# 6_SWITCHING.net
KiCad netlist of a schematic drawn in Altium Designer
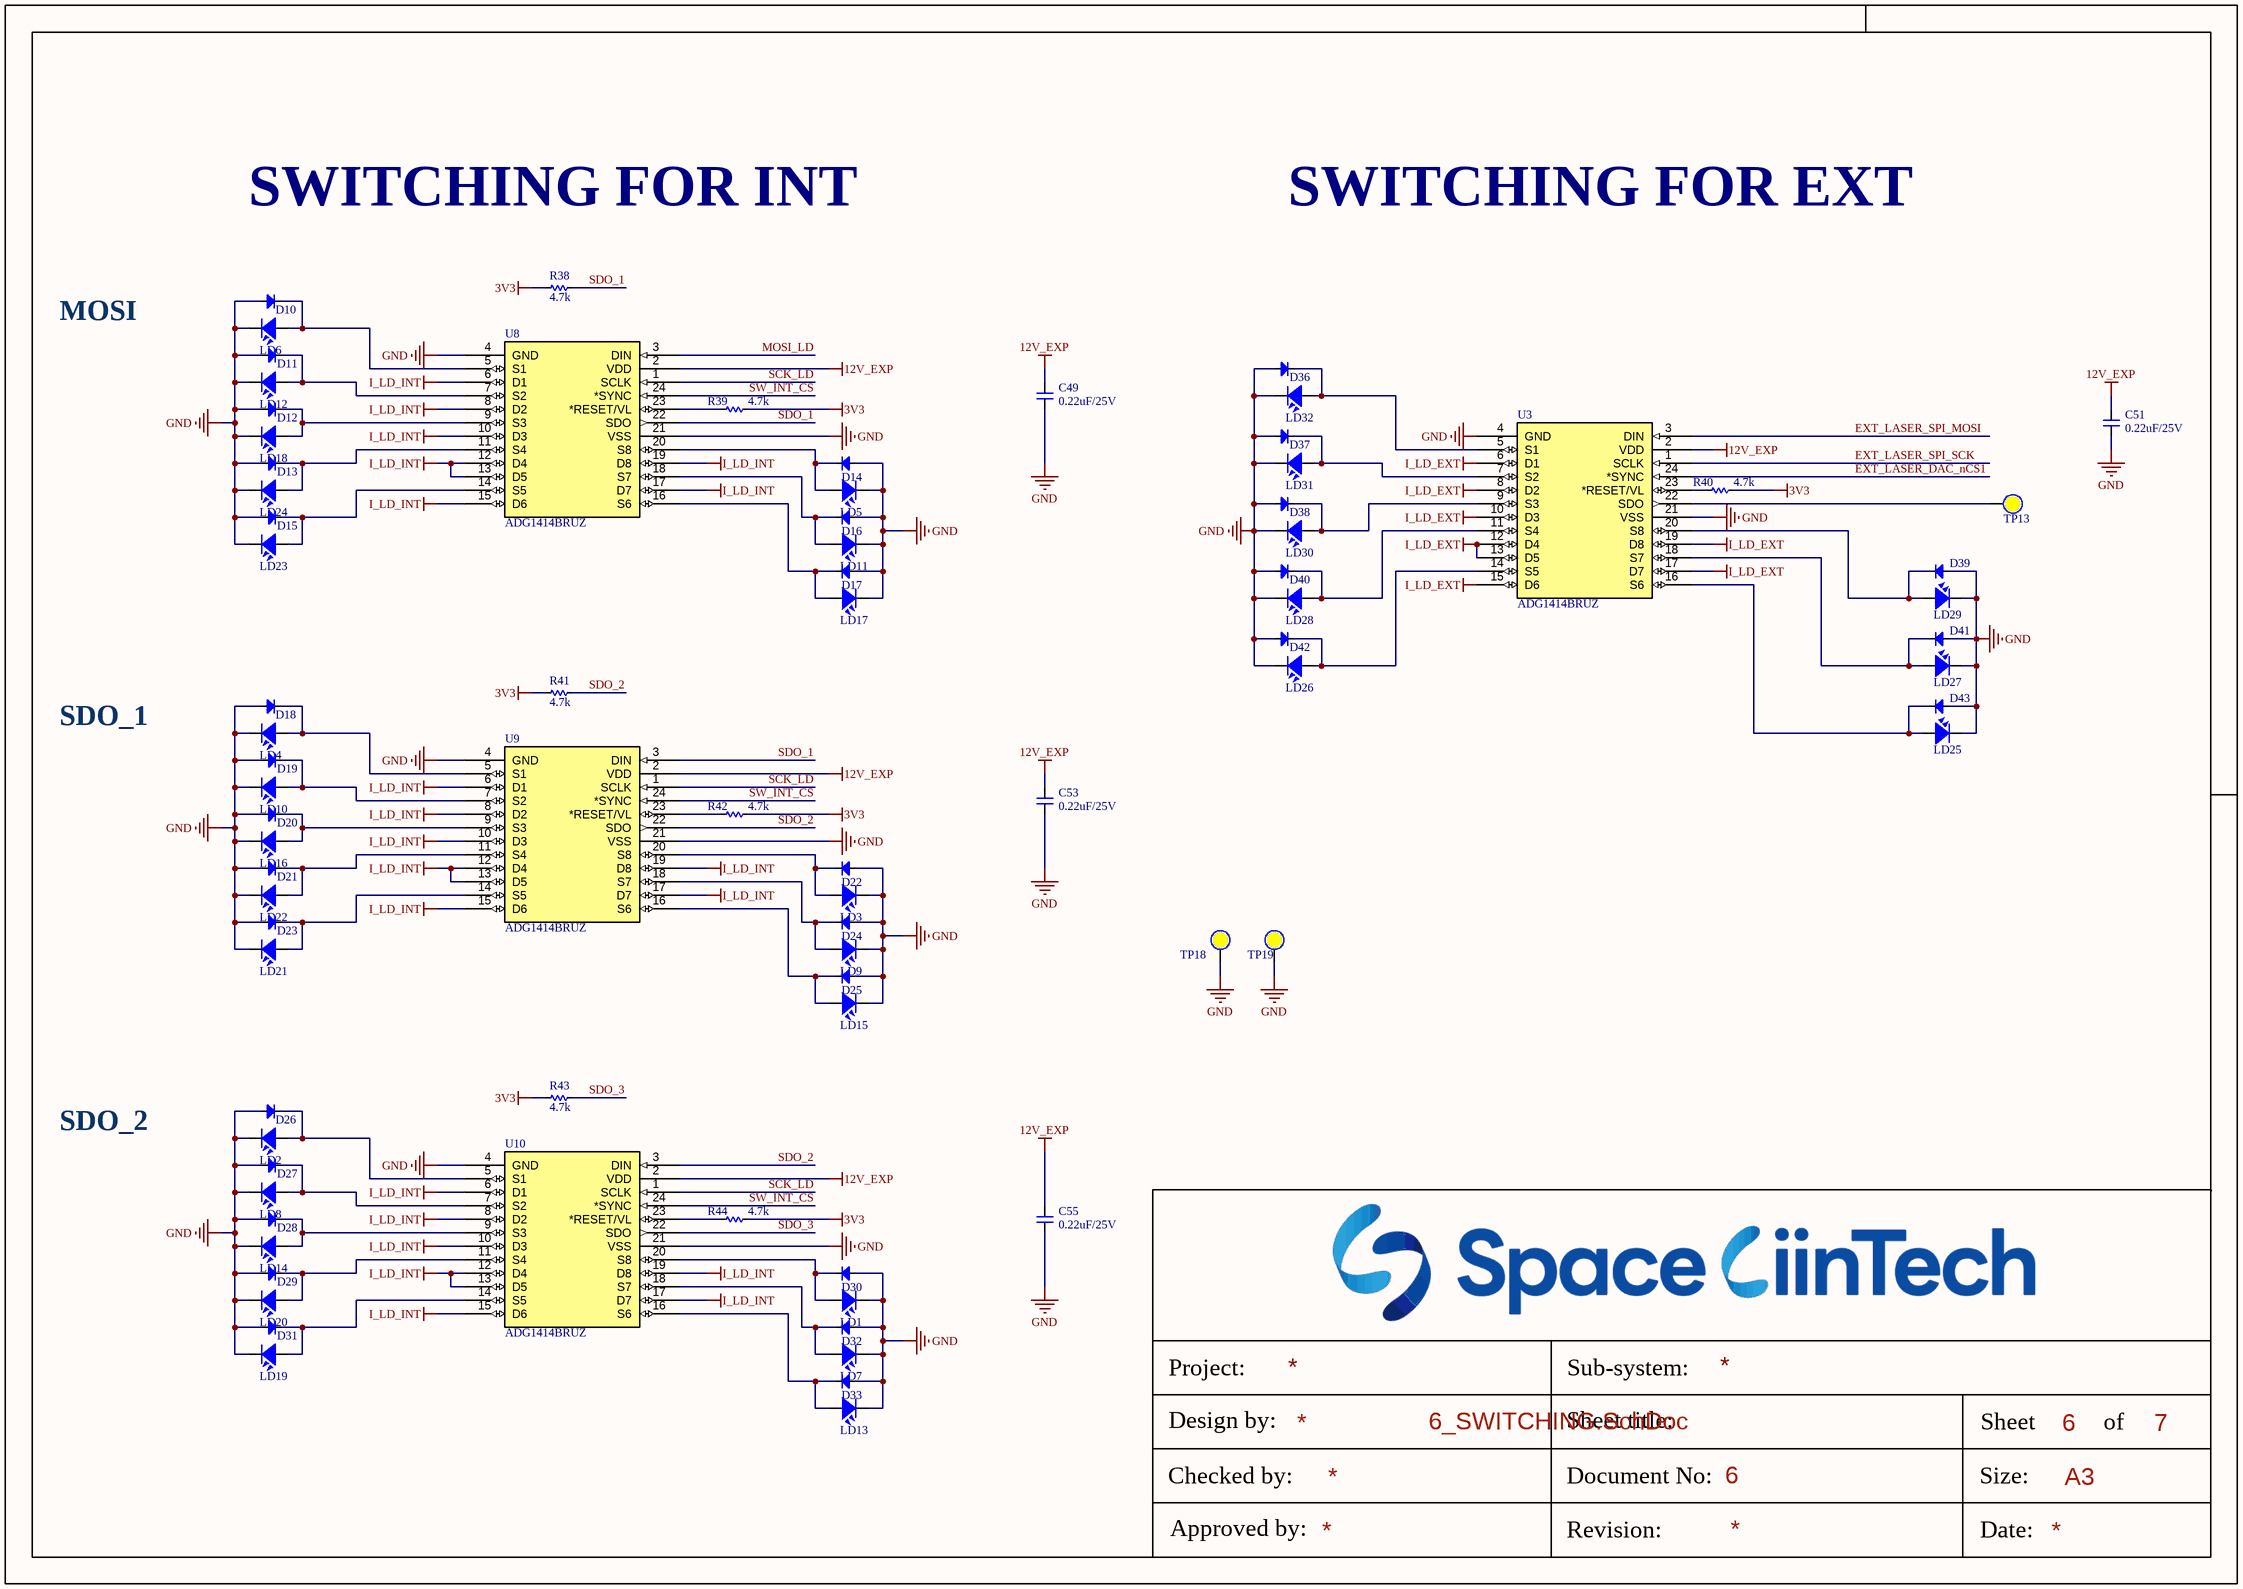
[diagram p0: 6_SWITCHING.SchDoc]

(export (version "E")
  (design (tool "Eeschema 10.0.6"))
  (components
    (comp (ref "C49")
      (value "0.22uF/25V")
      (footprint "CAP_C_1608X80")
      (description "CAP")
      (libsource (lib "LABLIB") (part "_CAP_C_2"))
    )
    (comp (ref "C51")
      (value "0.22uF/25V")
      (footprint "CAP_C_1608X80")
      (description "CAP")
      (libsource (lib "LABLIB") (part "_CAP_C_2"))
    )
    (comp (ref "C53")
      (value "0.22uF/25V")
      (footprint "CAP_C_1608X80")
      (description "CAP")
      (libsource (lib "LABLIB") (part "_CAP_C_2"))
    )
    (comp (ref "C55")
      (value "0.22uF/25V")
      (footprint "CAP_C_1608X80")
      (description "CAP")
      (libsource (lib "LABLIB") (part "_CAP_C_2"))
    )
    (comp (ref "D10")
      (value "1N4148W-TP")
      (footprint "SOD23")
      (fields (field (name "PUBLISHER") "Altium Limited"))
      (libsource (lib "LASER_LIB_SCHE") (part "Diode SMD"))
    )
    (comp (ref "D11")
      (value "1N4148W-TP")
      (footprint "SOD23")
      (fields (field (name "PUBLISHER") "Altium Limited"))
      (libsource (lib "LASER_LIB_SCHE") (part "Diode SMD"))
    )
    (comp (ref "D12")
      (value "1N4148W-TP")
      (footprint "SOD23")
      (fields (field (name "PUBLISHER") "Altium Limited"))
      (libsource (lib "LASER_LIB_SCHE") (part "Diode SMD"))
    )
    (comp (ref "D13")
      (value "1N4148W-TP")
      (footprint "SOD23")
      (fields (field (name "PUBLISHER") "Altium Limited"))
      (libsource (lib "LASER_LIB_SCHE") (part "Diode SMD"))
    )
    (comp (ref "D14")
      (value "1N4148W-TP")
      (footprint "SOD23")
      (fields (field (name "PUBLISHER") "Altium Limited"))
      (libsource (lib "LASER_LIB_SCHE") (part "Diode SMD"))
    )
    (comp (ref "D15")
      (value "1N4148W-TP")
      (footprint "SOD23")
      (fields (field (name "PUBLISHER") "Altium Limited"))
      (libsource (lib "LASER_LIB_SCHE") (part "Diode SMD"))
    )
    (comp (ref "D16")
      (value "1N4148W-TP")
      (footprint "SOD23")
      (fields (field (name "PUBLISHER") "Altium Limited"))
      (libsource (lib "LASER_LIB_SCHE") (part "Diode SMD"))
    )
    (comp (ref "D17")
      (value "1N4148W-TP")
      (footprint "SOD23")
      (fields (field (name "PUBLISHER") "Altium Limited"))
      (libsource (lib "LASER_LIB_SCHE") (part "Diode SMD"))
    )
    (comp (ref "D18")
      (value "1N4148W-TP")
      (footprint "SOD23")
      (fields (field (name "PUBLISHER") "Altium Limited"))
      (libsource (lib "LASER_LIB_SCHE") (part "Diode SMD"))
    )
    (comp (ref "D19")
      (value "1N4148W-TP")
      (footprint "SOD23")
      (fields (field (name "PUBLISHER") "Altium Limited"))
      (libsource (lib "LASER_LIB_SCHE") (part "Diode SMD"))
    )
    (comp (ref "D20")
      (value "1N4148W-TP")
      (footprint "SOD23")
      (fields (field (name "PUBLISHER") "Altium Limited"))
      (libsource (lib "LASER_LIB_SCHE") (part "Diode SMD"))
    )
    (comp (ref "D21")
      (value "1N4148W-TP")
      (footprint "SOD23")
      (fields (field (name "PUBLISHER") "Altium Limited"))
      (libsource (lib "LASER_LIB_SCHE") (part "Diode SMD"))
    )
    (comp (ref "D22")
      (value "1N4148W-TP")
      (footprint "SOD23")
      (fields (field (name "PUBLISHER") "Altium Limited"))
      (libsource (lib "LASER_LIB_SCHE") (part "Diode SMD"))
    )
    (comp (ref "D23")
      (value "1N4148W-TP")
      (footprint "SOD23")
      (fields (field (name "PUBLISHER") "Altium Limited"))
      (libsource (lib "LASER_LIB_SCHE") (part "Diode SMD"))
    )
    (comp (ref "D24")
      (value "1N4148W-TP")
      (footprint "SOD23")
      (fields (field (name "PUBLISHER") "Altium Limited"))
      (libsource (lib "LASER_LIB_SCHE") (part "Diode SMD"))
    )
    (comp (ref "D25")
      (value "1N4148W-TP")
      (footprint "SOD23")
      (fields (field (name "PUBLISHER") "Altium Limited"))
      (libsource (lib "LASER_LIB_SCHE") (part "Diode SMD"))
    )
    (comp (ref "D26")
      (value "1N4148W-TP")
      (footprint "SOD23")
      (fields (field (name "PUBLISHER") "Altium Limited"))
      (libsource (lib "LASER_LIB_SCHE") (part "Diode SMD"))
    )
    (comp (ref "D27")
      (value "1N4148W-TP")
      (footprint "SOD23")
      (fields (field (name "PUBLISHER") "Altium Limited"))
      (libsource (lib "LASER_LIB_SCHE") (part "Diode SMD"))
    )
    (comp (ref "D28")
      (value "1N4148W-TP")
      (footprint "SOD23")
      (fields (field (name "PUBLISHER") "Altium Limited"))
      (libsource (lib "LASER_LIB_SCHE") (part "Diode SMD"))
    )
    (comp (ref "D29")
      (value "1N4148W-TP")
      (footprint "SOD23")
      (fields (field (name "PUBLISHER") "Altium Limited"))
      (libsource (lib "LASER_LIB_SCHE") (part "Diode SMD"))
    )
    (comp (ref "D30")
      (value "1N4148W-TP")
      (footprint "SOD23")
      (fields (field (name "PUBLISHER") "Altium Limited"))
      (libsource (lib "LASER_LIB_SCHE") (part "Diode SMD"))
    )
    (comp (ref "D31")
      (value "1N4148W-TP")
      (footprint "SOD23")
      (fields (field (name "PUBLISHER") "Altium Limited"))
      (libsource (lib "LASER_LIB_SCHE") (part "Diode SMD"))
    )
    (comp (ref "D32")
      (value "1N4148W-TP")
      (footprint "SOD23")
      (fields (field (name "PUBLISHER") "Altium Limited"))
      (libsource (lib "LASER_LIB_SCHE") (part "Diode SMD"))
    )
    (comp (ref "D33")
      (value "1N4148W-TP")
      (footprint "SOD23")
      (fields (field (name "PUBLISHER") "Altium Limited"))
      (libsource (lib "LASER_LIB_SCHE") (part "Diode SMD"))
    )
    (comp (ref "D36")
      (value "1N4148W-TP")
      (footprint "SOD23")
      (fields (field (name "PUBLISHER") "Altium Limited"))
      (libsource (lib "LASER_LIB_SCHE") (part "Diode SMD"))
    )
    (comp (ref "D37")
      (value "1N4148W-TP")
      (footprint "SOD23")
      (fields (field (name "PUBLISHER") "Altium Limited"))
      (libsource (lib "LASER_LIB_SCHE") (part "Diode SMD"))
    )
    (comp (ref "D38")
      (value "1N4148W-TP")
      (footprint "SOD23")
      (fields (field (name "PUBLISHER") "Altium Limited"))
      (libsource (lib "LASER_LIB_SCHE") (part "Diode SMD"))
    )
    (comp (ref "D39")
      (value "1N4148W-TP")
      (footprint "SOD23")
      (fields (field (name "PUBLISHER") "Altium Limited"))
      (libsource (lib "LASER_LIB_SCHE") (part "Diode SMD"))
    )
    (comp (ref "D40")
      (value "1N4148W-TP")
      (footprint "SOD23")
      (fields (field (name "PUBLISHER") "Altium Limited"))
      (libsource (lib "LASER_LIB_SCHE") (part "Diode SMD"))
    )
    (comp (ref "D41")
      (value "1N4148W-TP")
      (footprint "SOD23")
      (fields (field (name "PUBLISHER") "Altium Limited"))
      (libsource (lib "LASER_LIB_SCHE") (part "Diode SMD"))
    )
    (comp (ref "D42")
      (value "1N4148W-TP")
      (footprint "SOD23")
      (fields (field (name "PUBLISHER") "Altium Limited"))
      (libsource (lib "LASER_LIB_SCHE") (part "Diode SMD"))
    )
    (comp (ref "D43")
      (value "1N4148W-TP")
      (footprint "SOD23")
      (fields (field (name "PUBLISHER") "Altium Limited"))
      (libsource (lib "LASER_LIB_SCHE") (part "Diode SMD"))
    )
    (comp (ref "LD1")
      (value "LaserDiode")
      (footprint "OPV302")
      (description "OPV302")
      (libsource (lib "LASER_LIB_SCHE") (part "LD"))
    )
    (comp (ref "LD2")
      (value "LaserDiode")
      (footprint "OPV302")
      (description "OPV302")
      (libsource (lib "LASER_LIB_SCHE") (part "LD"))
    )
    (comp (ref "LD3")
      (value "LaserDiode")
      (footprint "OPV302")
      (description "OPV302")
      (libsource (lib "LASER_LIB_SCHE") (part "LD"))
    )
    (comp (ref "LD4")
      (value "LaserDiode")
      (footprint "OPV302")
      (description "OPV302")
      (libsource (lib "LASER_LIB_SCHE") (part "LD"))
    )
    (comp (ref "LD5")
      (value "LaserDiode")
      (footprint "OPV302")
      (description "OPV302")
      (libsource (lib "LASER_LIB_SCHE") (part "LD"))
    )
    (comp (ref "LD6")
      (value "LaserDiode")
      (footprint "OPV302")
      (description "OPV302")
      (libsource (lib "LASER_LIB_SCHE") (part "LD"))
    )
    (comp (ref "LD7")
      (value "LaserDiode")
      (footprint "OPV302")
      (description "OPV302")
      (libsource (lib "LASER_LIB_SCHE") (part "LD"))
    )
    (comp (ref "LD8")
      (value "LaserDiode")
      (footprint "OPV302")
      (description "OPV302")
      (libsource (lib "LASER_LIB_SCHE") (part "LD"))
    )
    (comp (ref "LD9")
      (value "LaserDiode")
      (footprint "OPV302")
      (description "OPV302")
      (libsource (lib "LASER_LIB_SCHE") (part "LD"))
    )
    (comp (ref "LD10")
      (value "LaserDiode")
      (footprint "OPV302")
      (description "OPV302")
      (libsource (lib "LASER_LIB_SCHE") (part "LD"))
    )
    (comp (ref "LD11")
      (value "LaserDiode")
      (footprint "OPV302")
      (description "OPV302")
      (libsource (lib "LASER_LIB_SCHE") (part "LD"))
    )
    (comp (ref "LD12")
      (value "LaserDiode")
      (footprint "OPV302")
      (description "OPV302")
      (libsource (lib "LASER_LIB_SCHE") (part "LD"))
    )
    (comp (ref "LD13")
      (value "LaserDiode")
      (footprint "OPV302")
      (description "OPV302")
      (libsource (lib "LASER_LIB_SCHE") (part "LD"))
    )
    (comp (ref "LD14")
      (value "LaserDiode")
      (footprint "OPV302")
      (description "OPV302")
      (libsource (lib "LASER_LIB_SCHE") (part "LD"))
    )
    (comp (ref "LD15")
      (value "LaserDiode")
      (footprint "OPV302")
      (description "OPV302")
      (libsource (lib "LASER_LIB_SCHE") (part "LD"))
    )
    (comp (ref "LD16")
      (value "LaserDiode")
      (footprint "OPV302")
      (description "OPV302")
      (libsource (lib "LASER_LIB_SCHE") (part "LD"))
    )
    (comp (ref "LD17")
      (value "LaserDiode")
      (footprint "OPV302")
      (description "OPV302")
      (libsource (lib "LASER_LIB_SCHE") (part "LD"))
    )
    (comp (ref "LD18")
      (value "LaserDiode")
      (footprint "OPV302")
      (description "OPV302")
      (libsource (lib "LASER_LIB_SCHE") (part "LD"))
    )
    (comp (ref "LD19")
      (value "LaserDiode")
      (footprint "OPV302")
      (description "OPV302")
      (libsource (lib "LASER_LIB_SCHE") (part "LD"))
    )
    (comp (ref "LD20")
      (value "LaserDiode")
      (footprint "OPV302")
      (description "OPV302")
      (libsource (lib "LASER_LIB_SCHE") (part "LD"))
    )
    (comp (ref "LD21")
      (value "LaserDiode")
      (footprint "OPV302")
      (description "OPV302")
      (libsource (lib "LASER_LIB_SCHE") (part "LD"))
    )
    (comp (ref "LD22")
      (value "LaserDiode")
      (footprint "OPV302")
      (description "OPV302")
      (libsource (lib "LASER_LIB_SCHE") (part "LD"))
    )
    (comp (ref "LD23")
      (value "LaserDiode")
      (footprint "OPV302")
      (description "OPV302")
      (libsource (lib "LASER_LIB_SCHE") (part "LD"))
    )
    (comp (ref "LD24")
      (value "LaserDiode")
      (footprint "OPV302")
      (description "OPV302")
      (libsource (lib "LASER_LIB_SCHE") (part "LD"))
    )
    (comp (ref "LD25")
      (value "LaserDiode")
      (footprint "RLD65NZX1")
      (description "RLD65NZX1")
      (libsource (lib "LASER_LIB_SCHE") (part "LD_RLD65NZX1"))
    )
    (comp (ref "LD26")
      (value "LaserDiode")
      (footprint "RLD65NZX1")
      (description "RLD65NZX1")
      (libsource (lib "LASER_LIB_SCHE") (part "LD_RLD65NZX1"))
    )
    (comp (ref "LD27")
      (value "LaserDiode")
      (footprint "RLD65NZX1")
      (description "RLD65NZX1")
      (libsource (lib "LASER_LIB_SCHE") (part "LD_RLD65NZX1"))
    )
    (comp (ref "LD28")
      (value "LaserDiode")
      (footprint "RLD65NZX1")
      (description "RLD65NZX1")
      (libsource (lib "LASER_LIB_SCHE") (part "LD_RLD65NZX1"))
    )
    (comp (ref "LD29")
      (value "LaserDiode")
      (footprint "RLD65NZX1")
      (description "RLD65NZX1")
      (libsource (lib "LASER_LIB_SCHE") (part "LD_RLD65NZX1"))
    )
    (comp (ref "LD30")
      (value "LaserDiode")
      (footprint "RLD65NZX1")
      (description "RLD65NZX1")
      (libsource (lib "LASER_LIB_SCHE") (part "LD_RLD65NZX1"))
    )
    (comp (ref "LD31")
      (value "LaserDiode")
      (footprint "RLD65NZX1")
      (description "RLD65NZX1")
      (libsource (lib "LASER_LIB_SCHE") (part "LD_RLD65NZX1"))
    )
    (comp (ref "LD32")
      (value "LaserDiode")
      (footprint "RLD65NZX1")
      (description "RLD65NZX1")
      (libsource (lib "LASER_LIB_SCHE") (part "LD_RLD65NZX1"))
    )
    (comp (ref "R38")
      (value "4.7k")
      (footprint "RES_C_1608X60")
      (description "RES")
      (libsource (lib "LABLIB") (part "_RES_B_2"))
    )
    (comp (ref "R39")
      (value "4.7k")
      (footprint "RES_C_1608X60")
      (description "RES")
      (libsource (lib "LABLIB") (part "_RES_B_2"))
    )
    (comp (ref "R40")
      (value "4.7k")
      (footprint "RES_C_1608X60")
      (description "RES")
      (libsource (lib "LABLIB") (part "_RES_B_2"))
    )
    (comp (ref "R41")
      (value "4.7k")
      (footprint "RES_C_1608X60")
      (description "RES")
      (libsource (lib "LABLIB") (part "_RES_B_2"))
    )
    (comp (ref "R42")
      (value "4.7k")
      (footprint "RES_C_1608X60")
      (description "RES")
      (libsource (lib "LABLIB") (part "_RES_B_2"))
    )
    (comp (ref "R43")
      (value "4.7k")
      (footprint "RES_C_1608X60")
      (description "RES")
      (libsource (lib "LABLIB") (part "_RES_B_2"))
    )
    (comp (ref "R44")
      (value "4.7k")
      (footprint "RES_C_1608X60")
      (description "RES")
      (libsource (lib "LABLIB") (part "_RES_B_2"))
    )
    (comp (ref "TP13")
      (value "~")
      (footprint "Testpoint_80")
      (description "Test Point")
      (libsource (lib "LASER_LIB_SCHE") (part "Test Point"))
    )
    (comp (ref "TP18")
      (value "~")
      (footprint "Testpoint_80")
      (description "Test Point")
      (libsource (lib "") (part "Test Point_1"))
    )
    (comp (ref "TP19")
      (value "~")
      (footprint "Testpoint_80")
      (description "Test Point")
      (libsource (lib "") (part "Test Point_1"))
    )
    (comp (ref "U3")
      (value "ADG1414BRUZ")
      (footprint "TSSOP24")
      (libsource (lib "LASER_LIB_SCHE") (part "ADG1414BRUZ"))
    )
    (comp (ref "U8")
      (value "ADG1414BRUZ")
      (footprint "TSSOP24")
      (libsource (lib "LASER_LIB_SCHE") (part "ADG1414BRUZ"))
    )
    (comp (ref "U9")
      (value "ADG1414BRUZ")
      (footprint "TSSOP24")
      (libsource (lib "LASER_LIB_SCHE") (part "ADG1414BRUZ"))
    )
    (comp (ref "U10")
      (value "ADG1414BRUZ")
      (footprint "TSSOP24")
      (libsource (lib "LASER_LIB_SCHE") (part "ADG1414BRUZ"))
    )
  )
  (nets
    (net (code "1") (name "/EXT_LASER_DAC_nCS1") (class "Default")
      (node (ref "U3") (pin "24") (pinfunction "*SYNC_24") (pintype "input"))
    )
    (net (code "2") (name "/EXT_LASER_SPI_MOSI") (class "Default")
      (node (ref "U3") (pin "3") (pinfunction "DIN_3") (pintype "input"))
    )
    (net (code "3") (name "/EXT_LASER_SPI_SCK") (class "Default")
      (node (ref "U3") (pin "1") (pinfunction "SCLK_1") (pintype "input"))
    )
    (net (code "4") (name "/MOSI_LD") (class "Default")
      (node (ref "U8") (pin "3") (pinfunction "DIN_3") (pintype "input"))
    )
    (net (code "5") (name "/SCK_LD") (class "Default")
      (node (ref "U10") (pin "1") (pinfunction "SCLK_1") (pintype "input"))
      (node (ref "U8") (pin "1") (pinfunction "SCLK_1") (pintype "input"))
      (node (ref "U9") (pin "1") (pinfunction "SCLK_1") (pintype "input"))
    )
    (net (code "6") (name "/SDO_1") (class "Default")
      (node (ref "R38") (pin "2") (pinfunction "2_2") (pintype "passive"))
      (node (ref "U8") (pin "22") (pinfunction "SDO_22") (pintype "output"))
      (node (ref "U9") (pin "3") (pinfunction "DIN_3") (pintype "input"))
    )
    (net (code "7") (name "/SDO_2") (class "Default")
      (node (ref "R41") (pin "2") (pinfunction "2_2") (pintype "passive"))
      (node (ref "U10") (pin "3") (pinfunction "DIN_3") (pintype "input"))
      (node (ref "U9") (pin "22") (pinfunction "SDO_22") (pintype "output"))
    )
    (net (code "8") (name "/SDO_3") (class "Default")
      (node (ref "R43") (pin "2") (pinfunction "2_2") (pintype "passive"))
      (node (ref "U10") (pin "22") (pinfunction "SDO_22") (pintype "output"))
    )
    (net (code "9") (name "/SW_INT_CS") (class "Default")
      (node (ref "U10") (pin "24") (pinfunction "*SYNC_24") (pintype "input"))
      (node (ref "U8") (pin "24") (pinfunction "*SYNC_24") (pintype "input"))
      (node (ref "U9") (pin "24") (pinfunction "*SYNC_24") (pintype "input"))
    )
    (net (code "10") (name "3V3") (class "Default")
      (node (ref "R38") (pin "1") (pinfunction "1_1") (pintype "passive"))
      (node (ref "R39") (pin "2") (pinfunction "2_2") (pintype "passive"))
      (node (ref "R40") (pin "2") (pinfunction "2_2") (pintype "passive"))
      (node (ref "R41") (pin "1") (pinfunction "1_1") (pintype "passive"))
      (node (ref "R42") (pin "2") (pinfunction "2_2") (pintype "passive"))
      (node (ref "R43") (pin "1") (pinfunction "1_1") (pintype "passive"))
      (node (ref "R44") (pin "2") (pinfunction "2_2") (pintype "passive"))
    )
    (net (code "11") (name "12V_EXP") (class "Default")
      (node (ref "C49") (pin "2") (pinfunction "2_2") (pintype "passive"))
      (node (ref "C51") (pin "2") (pinfunction "2_2") (pintype "passive"))
      (node (ref "C53") (pin "2") (pinfunction "2_2") (pintype "passive"))
      (node (ref "C55") (pin "2") (pinfunction "2_2") (pintype "passive"))
      (node (ref "U10") (pin "2") (pinfunction "VDD_2") (pintype "power_in"))
      (node (ref "U3") (pin "2") (pinfunction "VDD_2") (pintype "power_in"))
      (node (ref "U8") (pin "2") (pinfunction "VDD_2") (pintype "power_in"))
      (node (ref "U9") (pin "2") (pinfunction "VDD_2") (pintype "power_in"))
    )
    (net (code "12") (name "GND") (class "Default")
      (node (ref "C49") (pin "1") (pinfunction "1_1") (pintype "passive"))
      (node (ref "C51") (pin "1") (pinfunction "1_1") (pintype "passive"))
      (node (ref "C53") (pin "1") (pinfunction "1_1") (pintype "passive"))
      (node (ref "C55") (pin "1") (pinfunction "1_1") (pintype "passive"))
      (node (ref "D10") (pin "1") (pinfunction "A_1") (pintype "passive"))
      (node (ref "D11") (pin "1") (pinfunction "A_1") (pintype "passive"))
      (node (ref "D12") (pin "1") (pinfunction "A_1") (pintype "passive"))
      (node (ref "D13") (pin "1") (pinfunction "A_1") (pintype "passive"))
      (node (ref "D14") (pin "1") (pinfunction "A_1") (pintype "passive"))
      (node (ref "D15") (pin "1") (pinfunction "A_1") (pintype "passive"))
      (node (ref "D16") (pin "1") (pinfunction "A_1") (pintype "passive"))
      (node (ref "D17") (pin "1") (pinfunction "A_1") (pintype "passive"))
      (node (ref "D18") (pin "1") (pinfunction "A_1") (pintype "passive"))
      (node (ref "D19") (pin "1") (pinfunction "A_1") (pintype "passive"))
      (node (ref "D20") (pin "1") (pinfunction "A_1") (pintype "passive"))
      (node (ref "D21") (pin "1") (pinfunction "A_1") (pintype "passive"))
      (node (ref "D22") (pin "1") (pinfunction "A_1") (pintype "passive"))
      (node (ref "D23") (pin "1") (pinfunction "A_1") (pintype "passive"))
      (node (ref "D24") (pin "1") (pinfunction "A_1") (pintype "passive"))
      (node (ref "D25") (pin "1") (pinfunction "A_1") (pintype "passive"))
      (node (ref "D26") (pin "1") (pinfunction "A_1") (pintype "passive"))
      (node (ref "D27") (pin "1") (pinfunction "A_1") (pintype "passive"))
      (node (ref "D28") (pin "1") (pinfunction "A_1") (pintype "passive"))
      (node (ref "D29") (pin "1") (pinfunction "A_1") (pintype "passive"))
      (node (ref "D30") (pin "1") (pinfunction "A_1") (pintype "passive"))
      (node (ref "D31") (pin "1") (pinfunction "A_1") (pintype "passive"))
      (node (ref "D32") (pin "1") (pinfunction "A_1") (pintype "passive"))
      (node (ref "D33") (pin "1") (pinfunction "A_1") (pintype "passive"))
      (node (ref "D36") (pin "1") (pinfunction "A_1") (pintype "passive"))
      (node (ref "D37") (pin "1") (pinfunction "A_1") (pintype "passive"))
      (node (ref "D38") (pin "1") (pinfunction "A_1") (pintype "passive"))
      (node (ref "D39") (pin "1") (pinfunction "A_1") (pintype "passive"))
      (node (ref "D40") (pin "1") (pinfunction "A_1") (pintype "passive"))
      (node (ref "D41") (pin "1") (pinfunction "A_1") (pintype "passive"))
      (node (ref "D42") (pin "1") (pinfunction "A_1") (pintype "passive"))
      (node (ref "D43") (pin "1") (pinfunction "A_1") (pintype "passive"))
      (node (ref "LD1") (pin "2") (pinfunction "2_2") (pintype "passive"))
      (node (ref "LD10") (pin "2") (pinfunction "2_2") (pintype "passive"))
      (node (ref "LD11") (pin "2") (pinfunction "2_2") (pintype "passive"))
      (node (ref "LD12") (pin "2") (pinfunction "2_2") (pintype "passive"))
      (node (ref "LD13") (pin "2") (pinfunction "2_2") (pintype "passive"))
      (node (ref "LD14") (pin "2") (pinfunction "2_2") (pintype "passive"))
      (node (ref "LD15") (pin "2") (pinfunction "2_2") (pintype "passive"))
      (node (ref "LD16") (pin "2") (pinfunction "2_2") (pintype "passive"))
      (node (ref "LD17") (pin "2") (pinfunction "2_2") (pintype "passive"))
      (node (ref "LD18") (pin "2") (pinfunction "2_2") (pintype "passive"))
      (node (ref "LD19") (pin "2") (pinfunction "2_2") (pintype "passive"))
      (node (ref "LD2") (pin "2") (pinfunction "2_2") (pintype "passive"))
      (node (ref "LD20") (pin "2") (pinfunction "2_2") (pintype "passive"))
      (node (ref "LD21") (pin "2") (pinfunction "2_2") (pintype "passive"))
      (node (ref "LD22") (pin "2") (pinfunction "2_2") (pintype "passive"))
      (node (ref "LD23") (pin "2") (pinfunction "2_2") (pintype "passive"))
      (node (ref "LD24") (pin "2") (pinfunction "2_2") (pintype "passive"))
      (node (ref "LD25") (pin "1") (pinfunction "1_1") (pintype "passive"))
      (node (ref "LD26") (pin "1") (pinfunction "1_1") (pintype "passive"))
      (node (ref "LD27") (pin "1") (pinfunction "1_1") (pintype "passive"))
      (node (ref "LD28") (pin "1") (pinfunction "1_1") (pintype "passive"))
      (node (ref "LD29") (pin "1") (pinfunction "1_1") (pintype "passive"))
      (node (ref "LD3") (pin "2") (pinfunction "2_2") (pintype "passive"))
      (node (ref "LD30") (pin "1") (pinfunction "1_1") (pintype "passive"))
      (node (ref "LD31") (pin "1") (pinfunction "1_1") (pintype "passive"))
      (node (ref "LD32") (pin "1") (pinfunction "1_1") (pintype "passive"))
      (node (ref "LD4") (pin "2") (pinfunction "2_2") (pintype "passive"))
      (node (ref "LD5") (pin "2") (pinfunction "2_2") (pintype "passive"))
      (node (ref "LD6") (pin "2") (pinfunction "2_2") (pintype "passive"))
      (node (ref "LD7") (pin "2") (pinfunction "2_2") (pintype "passive"))
      (node (ref "LD8") (pin "2") (pinfunction "2_2") (pintype "passive"))
      (node (ref "LD9") (pin "2") (pinfunction "2_2") (pintype "passive"))
      (node (ref "TP18") (pin "1") (pinfunction "1_1") (pintype "passive"))
      (node (ref "TP19") (pin "1") (pinfunction "1_1") (pintype "passive"))
      (node (ref "U10") (pin "21") (pinfunction "VSS_21") (pintype "power_in"))
      (node (ref "U10") (pin "4") (pinfunction "GND_4") (pintype "power_in"))
      (node (ref "U3") (pin "21") (pinfunction "VSS_21") (pintype "power_in"))
      (node (ref "U3") (pin "4") (pinfunction "GND_4") (pintype "power_in"))
      (node (ref "U8") (pin "21") (pinfunction "VSS_21") (pintype "power_in"))
      (node (ref "U8") (pin "4") (pinfunction "GND_4") (pintype "power_in"))
      (node (ref "U9") (pin "21") (pinfunction "VSS_21") (pintype "power_in"))
      (node (ref "U9") (pin "4") (pinfunction "GND_4") (pintype "power_in"))
    )
    (net (code "13") (name "I_LD_EXT") (class "Default")
      (node (ref "U3") (pin "10") (pinfunction "D3_10") (pintype "bidirectional"))
      (node (ref "U3") (pin "12") (pinfunction "D4_12") (pintype "bidirectional"))
      (node (ref "U3") (pin "13") (pinfunction "D5_13") (pintype "bidirectional"))
      (node (ref "U3") (pin "15") (pinfunction "D6_15") (pintype "bidirectional"))
      (node (ref "U3") (pin "17") (pinfunction "D7_17") (pintype "bidirectional"))
      (node (ref "U3") (pin "19") (pinfunction "D8_19") (pintype "bidirectional"))
      (node (ref "U3") (pin "6") (pinfunction "D1_6") (pintype "bidirectional"))
      (node (ref "U3") (pin "8") (pinfunction "D2_8") (pintype "bidirectional"))
    )
    (net (code "14") (name "I_LD_INT") (class "Default")
      (node (ref "U10") (pin "10") (pinfunction "D3_10") (pintype "bidirectional"))
      (node (ref "U10") (pin "12") (pinfunction "D4_12") (pintype "bidirectional"))
      (node (ref "U10") (pin "13") (pinfunction "D5_13") (pintype "bidirectional"))
      (node (ref "U10") (pin "15") (pinfunction "D6_15") (pintype "bidirectional"))
      (node (ref "U10") (pin "17") (pinfunction "D7_17") (pintype "bidirectional"))
      (node (ref "U10") (pin "19") (pinfunction "D8_19") (pintype "bidirectional"))
      (node (ref "U10") (pin "6") (pinfunction "D1_6") (pintype "bidirectional"))
      (node (ref "U10") (pin "8") (pinfunction "D2_8") (pintype "bidirectional"))
      (node (ref "U8") (pin "10") (pinfunction "D3_10") (pintype "bidirectional"))
      (node (ref "U8") (pin "12") (pinfunction "D4_12") (pintype "bidirectional"))
      (node (ref "U8") (pin "13") (pinfunction "D5_13") (pintype "bidirectional"))
      (node (ref "U8") (pin "15") (pinfunction "D6_15") (pintype "bidirectional"))
      (node (ref "U8") (pin "17") (pinfunction "D7_17") (pintype "bidirectional"))
      (node (ref "U8") (pin "19") (pinfunction "D8_19") (pintype "bidirectional"))
      (node (ref "U8") (pin "6") (pinfunction "D1_6") (pintype "bidirectional"))
      (node (ref "U8") (pin "8") (pinfunction "D2_8") (pintype "bidirectional"))
      (node (ref "U9") (pin "10") (pinfunction "D3_10") (pintype "bidirectional"))
      (node (ref "U9") (pin "12") (pinfunction "D4_12") (pintype "bidirectional"))
      (node (ref "U9") (pin "13") (pinfunction "D5_13") (pintype "bidirectional"))
      (node (ref "U9") (pin "15") (pinfunction "D6_15") (pintype "bidirectional"))
      (node (ref "U9") (pin "17") (pinfunction "D7_17") (pintype "bidirectional"))
      (node (ref "U9") (pin "19") (pinfunction "D8_19") (pintype "bidirectional"))
      (node (ref "U9") (pin "6") (pinfunction "D1_6") (pintype "bidirectional"))
      (node (ref "U9") (pin "8") (pinfunction "D2_8") (pintype "bidirectional"))
    )
    (net (code "15") (name "Net-(D10-K)") (class "Default")
      (node (ref "D10") (pin "2") (pinfunction "K_2") (pintype "passive"))
      (node (ref "LD6") (pin "1") (pinfunction "1_1") (pintype "passive"))
      (node (ref "U8") (pin "5") (pinfunction "S1_5") (pintype "bidirectional"))
    )
    (net (code "16") (name "Net-(D11-K)") (class "Default")
      (node (ref "D11") (pin "2") (pinfunction "K_2") (pintype "passive"))
      (node (ref "LD12") (pin "1") (pinfunction "1_1") (pintype "passive"))
      (node (ref "U8") (pin "7") (pinfunction "S2_7") (pintype "bidirectional"))
    )
    (net (code "17") (name "Net-(D12-K)") (class "Default")
      (node (ref "D12") (pin "2") (pinfunction "K_2") (pintype "passive"))
      (node (ref "LD18") (pin "1") (pinfunction "1_1") (pintype "passive"))
      (node (ref "U8") (pin "9") (pinfunction "S3_9") (pintype "bidirectional"))
    )
    (net (code "18") (name "Net-(D13-K)") (class "Default")
      (node (ref "D13") (pin "2") (pinfunction "K_2") (pintype "passive"))
      (node (ref "LD24") (pin "1") (pinfunction "1_1") (pintype "passive"))
      (node (ref "U8") (pin "11") (pinfunction "S4_11") (pintype "bidirectional"))
    )
    (net (code "19") (name "Net-(D14-K)") (class "Default")
      (node (ref "D14") (pin "2") (pinfunction "K_2") (pintype "passive"))
      (node (ref "LD5") (pin "1") (pinfunction "1_1") (pintype "passive"))
      (node (ref "U8") (pin "20") (pinfunction "S8_20") (pintype "bidirectional"))
    )
    (net (code "20") (name "Net-(D15-K)") (class "Default")
      (node (ref "D15") (pin "2") (pinfunction "K_2") (pintype "passive"))
      (node (ref "LD23") (pin "1") (pinfunction "1_1") (pintype "passive"))
      (node (ref "U8") (pin "14") (pinfunction "S5_14") (pintype "bidirectional"))
    )
    (net (code "21") (name "Net-(D16-K)") (class "Default")
      (node (ref "D16") (pin "2") (pinfunction "K_2") (pintype "passive"))
      (node (ref "LD11") (pin "1") (pinfunction "1_1") (pintype "passive"))
      (node (ref "U8") (pin "18") (pinfunction "S7_18") (pintype "bidirectional"))
    )
    (net (code "22") (name "Net-(D17-K)") (class "Default")
      (node (ref "D17") (pin "2") (pinfunction "K_2") (pintype "passive"))
      (node (ref "LD17") (pin "1") (pinfunction "1_1") (pintype "passive"))
      (node (ref "U8") (pin "16") (pinfunction "S6_16") (pintype "bidirectional"))
    )
    (net (code "23") (name "Net-(D18-K)") (class "Default")
      (node (ref "D18") (pin "2") (pinfunction "K_2") (pintype "passive"))
      (node (ref "LD4") (pin "1") (pinfunction "1_1") (pintype "passive"))
      (node (ref "U9") (pin "5") (pinfunction "S1_5") (pintype "bidirectional"))
    )
    (net (code "24") (name "Net-(D19-K)") (class "Default")
      (node (ref "D19") (pin "2") (pinfunction "K_2") (pintype "passive"))
      (node (ref "LD10") (pin "1") (pinfunction "1_1") (pintype "passive"))
      (node (ref "U9") (pin "7") (pinfunction "S2_7") (pintype "bidirectional"))
    )
    (net (code "25") (name "Net-(D20-K)") (class "Default")
      (node (ref "D20") (pin "2") (pinfunction "K_2") (pintype "passive"))
      (node (ref "LD16") (pin "1") (pinfunction "1_1") (pintype "passive"))
      (node (ref "U9") (pin "9") (pinfunction "S3_9") (pintype "bidirectional"))
    )
    (net (code "26") (name "Net-(D21-K)") (class "Default")
      (node (ref "D21") (pin "2") (pinfunction "K_2") (pintype "passive"))
      (node (ref "LD22") (pin "1") (pinfunction "1_1") (pintype "passive"))
      (node (ref "U9") (pin "11") (pinfunction "S4_11") (pintype "bidirectional"))
    )
    (net (code "27") (name "Net-(D22-K)") (class "Default")
      (node (ref "D22") (pin "2") (pinfunction "K_2") (pintype "passive"))
      (node (ref "LD3") (pin "1") (pinfunction "1_1") (pintype "passive"))
      (node (ref "U9") (pin "20") (pinfunction "S8_20") (pintype "bidirectional"))
    )
    (net (code "28") (name "Net-(D23-K)") (class "Default")
      (node (ref "D23") (pin "2") (pinfunction "K_2") (pintype "passive"))
      (node (ref "LD21") (pin "1") (pinfunction "1_1") (pintype "passive"))
      (node (ref "U9") (pin "14") (pinfunction "S5_14") (pintype "bidirectional"))
    )
    (net (code "29") (name "Net-(D24-K)") (class "Default")
      (node (ref "D24") (pin "2") (pinfunction "K_2") (pintype "passive"))
      (node (ref "LD9") (pin "1") (pinfunction "1_1") (pintype "passive"))
      (node (ref "U9") (pin "18") (pinfunction "S7_18") (pintype "bidirectional"))
    )
    (net (code "30") (name "Net-(D25-K)") (class "Default")
      (node (ref "D25") (pin "2") (pinfunction "K_2") (pintype "passive"))
      (node (ref "LD15") (pin "1") (pinfunction "1_1") (pintype "passive"))
      (node (ref "U9") (pin "16") (pinfunction "S6_16") (pintype "bidirectional"))
    )
    (net (code "31") (name "Net-(D26-K)") (class "Default")
      (node (ref "D26") (pin "2") (pinfunction "K_2") (pintype "passive"))
      (node (ref "LD2") (pin "1") (pinfunction "1_1") (pintype "passive"))
      (node (ref "U10") (pin "5") (pinfunction "S1_5") (pintype "bidirectional"))
    )
    (net (code "32") (name "Net-(D27-K)") (class "Default")
      (node (ref "D27") (pin "2") (pinfunction "K_2") (pintype "passive"))
      (node (ref "LD8") (pin "1") (pinfunction "1_1") (pintype "passive"))
      (node (ref "U10") (pin "7") (pinfunction "S2_7") (pintype "bidirectional"))
    )
    (net (code "33") (name "Net-(D28-K)") (class "Default")
      (node (ref "D28") (pin "2") (pinfunction "K_2") (pintype "passive"))
      (node (ref "LD14") (pin "1") (pinfunction "1_1") (pintype "passive"))
      (node (ref "U10") (pin "9") (pinfunction "S3_9") (pintype "bidirectional"))
    )
    (net (code "34") (name "Net-(D29-K)") (class "Default")
      (node (ref "D29") (pin "2") (pinfunction "K_2") (pintype "passive"))
      (node (ref "LD20") (pin "1") (pinfunction "1_1") (pintype "passive"))
      (node (ref "U10") (pin "11") (pinfunction "S4_11") (pintype "bidirectional"))
    )
    (net (code "35") (name "Net-(D30-K)") (class "Default")
      (node (ref "D30") (pin "2") (pinfunction "K_2") (pintype "passive"))
      (node (ref "LD1") (pin "1") (pinfunction "1_1") (pintype "passive"))
      (node (ref "U10") (pin "20") (pinfunction "S8_20") (pintype "bidirectional"))
    )
    (net (code "36") (name "Net-(D31-K)") (class "Default")
      (node (ref "D31") (pin "2") (pinfunction "K_2") (pintype "passive"))
      (node (ref "LD19") (pin "1") (pinfunction "1_1") (pintype "passive"))
      (node (ref "U10") (pin "14") (pinfunction "S5_14") (pintype "bidirectional"))
    )
    (net (code "37") (name "Net-(D32-K)") (class "Default")
      (node (ref "D32") (pin "2") (pinfunction "K_2") (pintype "passive"))
      (node (ref "LD7") (pin "1") (pinfunction "1_1") (pintype "passive"))
      (node (ref "U10") (pin "18") (pinfunction "S7_18") (pintype "bidirectional"))
    )
    (net (code "38") (name "Net-(D33-K)") (class "Default")
      (node (ref "D33") (pin "2") (pinfunction "K_2") (pintype "passive"))
      (node (ref "LD13") (pin "1") (pinfunction "1_1") (pintype "passive"))
      (node (ref "U10") (pin "16") (pinfunction "S6_16") (pintype "bidirectional"))
    )
    (net (code "39") (name "Net-(D36-K)") (class "Default")
      (node (ref "D36") (pin "2") (pinfunction "K_2") (pintype "passive"))
      (node (ref "LD32") (pin "3") (pinfunction "3_3") (pintype "passive"))
      (node (ref "U3") (pin "5") (pinfunction "S1_5") (pintype "bidirectional"))
    )
    (net (code "40") (name "Net-(D37-K)") (class "Default")
      (node (ref "D37") (pin "2") (pinfunction "K_2") (pintype "passive"))
      (node (ref "LD31") (pin "3") (pinfunction "3_3") (pintype "passive"))
      (node (ref "U3") (pin "7") (pinfunction "S2_7") (pintype "bidirectional"))
    )
    (net (code "41") (name "Net-(D38-K)") (class "Default")
      (node (ref "D38") (pin "2") (pinfunction "K_2") (pintype "passive"))
      (node (ref "LD30") (pin "3") (pinfunction "3_3") (pintype "passive"))
      (node (ref "U3") (pin "9") (pinfunction "S3_9") (pintype "bidirectional"))
    )
    (net (code "42") (name "Net-(D39-K)") (class "Default")
      (node (ref "D39") (pin "2") (pinfunction "K_2") (pintype "passive"))
      (node (ref "LD29") (pin "3") (pinfunction "3_3") (pintype "passive"))
      (node (ref "U3") (pin "20") (pinfunction "S8_20") (pintype "bidirectional"))
    )
    (net (code "43") (name "Net-(D40-K)") (class "Default")
      (node (ref "D40") (pin "2") (pinfunction "K_2") (pintype "passive"))
      (node (ref "LD28") (pin "3") (pinfunction "3_3") (pintype "passive"))
      (node (ref "U3") (pin "11") (pinfunction "S4_11") (pintype "bidirectional"))
    )
    (net (code "44") (name "Net-(D41-K)") (class "Default")
      (node (ref "D41") (pin "2") (pinfunction "K_2") (pintype "passive"))
      (node (ref "LD27") (pin "3") (pinfunction "3_3") (pintype "passive"))
      (node (ref "U3") (pin "18") (pinfunction "S7_18") (pintype "bidirectional"))
    )
    (net (code "45") (name "Net-(D42-K)") (class "Default")
      (node (ref "D42") (pin "2") (pinfunction "K_2") (pintype "passive"))
      (node (ref "LD26") (pin "3") (pinfunction "3_3") (pintype "passive"))
      (node (ref "U3") (pin "14") (pinfunction "S5_14") (pintype "bidirectional"))
    )
    (net (code "46") (name "Net-(D43-K)") (class "Default")
      (node (ref "D43") (pin "2") (pinfunction "K_2") (pintype "passive"))
      (node (ref "LD25") (pin "3") (pinfunction "3_3") (pintype "passive"))
      (node (ref "U3") (pin "16") (pinfunction "S6_16") (pintype "bidirectional"))
    )
    (net (code "47") (name "Net-(U3-*RESET{slash}VL)") (class "Default")
      (node (ref "R40") (pin "1") (pinfunction "1_1") (pintype "passive"))
      (node (ref "U3") (pin "23") (pinfunction "*RESET/VL_23") (pintype "bidirectional"))
    )
    (net (code "48") (name "Net-(U3-SDO)") (class "Default")
      (node (ref "TP13") (pin "1") (pinfunction "1_1") (pintype "passive"))
      (node (ref "U3") (pin "22") (pinfunction "SDO_22") (pintype "output"))
    )
    (net (code "49") (name "Net-(U8-*RESET{slash}VL)") (class "Default")
      (node (ref "R39") (pin "1") (pinfunction "1_1") (pintype "passive"))
      (node (ref "U8") (pin "23") (pinfunction "*RESET/VL_23") (pintype "bidirectional"))
    )
    (net (code "50") (name "Net-(U9-*RESET{slash}VL)") (class "Default")
      (node (ref "R42") (pin "1") (pinfunction "1_1") (pintype "passive"))
      (node (ref "U9") (pin "23") (pinfunction "*RESET/VL_23") (pintype "bidirectional"))
    )
    (net (code "51") (name "Net-(U10-*RESET{slash}VL)") (class "Default")
      (node (ref "R44") (pin "1") (pinfunction "1_1") (pintype "passive"))
      (node (ref "U10") (pin "23") (pinfunction "*RESET/VL_23") (pintype "bidirectional"))
    )
  )
)
